# 04-TFCard_SU03T.net
KiCad netlist of a schematic drawn in Altium Designer
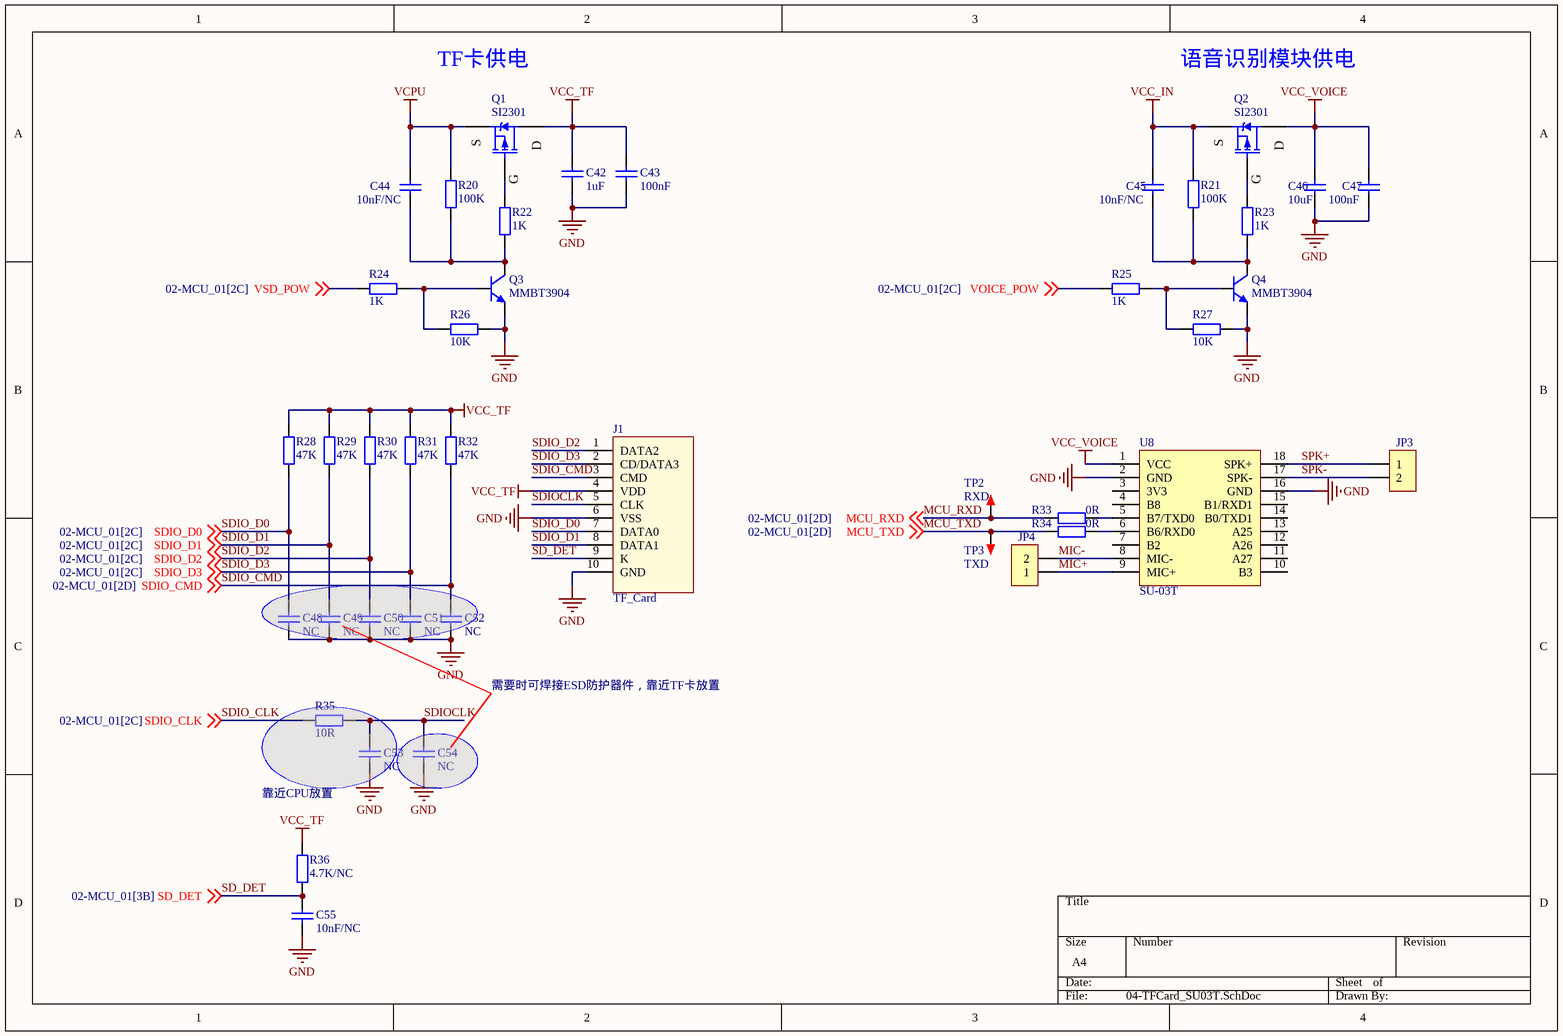
[diagram p0: 04-TFCard_SU03T.SchDoc]

(export (version "E")
  (design (tool "Eeschema 10.0.6"))
  (components
    (comp (ref "C42")
      (value "1uF")
      (footprint "C0603_M")
      (description "贴片电容/MLCC电容")
      (libsource (lib "0.1 - 电阻-电容-电感-保险丝-晶振-晶体-磁珠-电位器-法拉电容-馈通电容") (part "C"))
    )
    (comp (ref "C43")
      (value "100nF")
      (footprint "C0603_M")
      (description "贴片电容/MLCC电容")
      (libsource (lib "0.1 - 电阻-电容-电感-保险丝-晶振-晶体-磁珠-电位器-法拉电容-馈通电容") (part "C"))
    )
    (comp (ref "C44")
      (value "10nF/NC")
      (footprint "C0603_M")
      (description "贴片电容/MLCC电容")
      (libsource (lib "0.1 - 电阻-电容-电感-保险丝-晶振-晶体-磁珠-电位器-法拉电容-馈通电容") (part "C"))
    )
    (comp (ref "C45")
      (value "10nF/NC")
      (footprint "C0603_M")
      (description "贴片电容/MLCC电容")
      (libsource (lib "0.1 - 电阻-电容-电感-保险丝-晶振-晶体-磁珠-电位器-法拉电容-馈通电容") (part "C"))
    )
    (comp (ref "C46")
      (value "10uF")
      (footprint "C0603_M")
      (description "贴片电容/MLCC电容")
      (libsource (lib "0.1 - 电阻-电容-电感-保险丝-晶振-晶体-磁珠-电位器-法拉电容-馈通电容") (part "C"))
    )
    (comp (ref "C47")
      (value "100nF")
      (footprint "C0603_M")
      (description "贴片电容/MLCC电容")
      (libsource (lib "0.1 - 电阻-电容-电感-保险丝-晶振-晶体-磁珠-电位器-法拉电容-馈通电容") (part "C"))
    )
    (comp (ref "C48")
      (value "NC")
      (footprint "C0402_L")
      (description "贴片电容/MLCC电容")
      (libsource (lib "0.1 - 电阻-电容-电感-保险丝-晶振-晶体-磁珠-电位器-法拉电容-馈通电容") (part "C"))
    )
    (comp (ref "C49")
      (value "NC")
      (footprint "C0402_L")
      (description "贴片电容/MLCC电容")
      (libsource (lib "0.1 - 电阻-电容-电感-保险丝-晶振-晶体-磁珠-电位器-法拉电容-馈通电容") (part "C"))
    )
    (comp (ref "C50")
      (value "NC")
      (footprint "C0402_L")
      (description "贴片电容/MLCC电容")
      (libsource (lib "0.1 - 电阻-电容-电感-保险丝-晶振-晶体-磁珠-电位器-法拉电容-馈通电容") (part "C"))
    )
    (comp (ref "C51")
      (value "NC")
      (footprint "C0402_L")
      (description "贴片电容/MLCC电容")
      (libsource (lib "0.1 - 电阻-电容-电感-保险丝-晶振-晶体-磁珠-电位器-法拉电容-馈通电容") (part "C"))
    )
    (comp (ref "C52")
      (value "NC")
      (footprint "C0402_L")
      (description "贴片电容/MLCC电容")
      (libsource (lib "0.1 - 电阻-电容-电感-保险丝-晶振-晶体-磁珠-电位器-法拉电容-馈通电容") (part "C"))
    )
    (comp (ref "C53")
      (value "NC")
      (footprint "C0603_M")
      (description "贴片电容/MLCC电容")
      (libsource (lib "0.1 - 电阻-电容-电感-保险丝-晶振-晶体-磁珠-电位器-法拉电容-馈通电容") (part "C"))
    )
    (comp (ref "C54")
      (value "NC")
      (footprint "C0402_L")
      (description "贴片电容/MLCC电容")
      (libsource (lib "0.1 - 电阻-电容-电感-保险丝-晶振-晶体-磁珠-电位器-法拉电容-馈通电容") (part "C"))
    )
    (comp (ref "C55")
      (value "10nF/NC")
      (footprint "C0603_M")
      (description "贴片电容/MLCC电容")
      (libsource (lib "0.1 - 电阻-电容-电感-保险丝-晶振-晶体-磁珠-电位器-法拉电容-馈通电容") (part "C"))
    )
    (comp (ref "J1")
      (value "TF_Card")
      (footprint "Micro SD")
      (description "TF卡座")
      (libsource (lib "0.6 - 电源_音频_USB Type-C_HDMI_XT60_5557_D-SUB_RJ45_SD-TF_SIM插座") (part "TF_Card"))
    )
    (comp (ref "JP3")
      (value "HDR-1X2")
      (footprint "MX1.25-WT-2P")
      (description "2P连接器")
      (libsource (lib "5.1 - 1.25mm连接器(FPC1.25_GH1.25_MX1.25)") (part "Header 2"))
    )
    (comp (ref "JP4")
      (value "HDR-1X2")
      (footprint "MX1.25-WT-2P")
      (description "2P连接器")
      (libsource (lib "") (part "Header 2_1"))
    )
    (comp (ref "Q1")
      (value "SI2301")
      (footprint "SOT23-3N")
      (description "P沟道 20V/2.8A")
      (libsource (lib "0.4 - 三极管-场效应管-可控硅") (part "SI2301"))
    )
    (comp (ref "Q2")
      (value "SI2301")
      (footprint "SOT23-3N")
      (description "P沟道 20V/2.8A")
      (libsource (lib "0.4 - 三极管-场效应管-可控硅") (part "SI2301"))
    )
    (comp (ref "Q3")
      (value "MMBT3904")
      (footprint "SOT23-3N")
      (description "高频放大-NPN型")
      (libsource (lib "0.4 - 三极管-场效应管-可控硅") (part "MMBT3904"))
    )
    (comp (ref "Q4")
      (value "MMBT3904")
      (footprint "SOT23-3N")
      (description "高频放大-NPN型")
      (libsource (lib "0.4 - 三极管-场效应管-可控硅") (part "MMBT3904"))
    )
    (comp (ref "R20")
      (value "100K")
      (footprint "R0603_M")
      (description "贴片电阻")
      (libsource (lib "0.1 - 电阻-电容-电感-保险丝-晶振-晶体-磁珠-电位器-法拉电容-馈通电容") (part "R"))
    )
    (comp (ref "R21")
      (value "100K")
      (footprint "R0603_M")
      (description "贴片电阻")
      (libsource (lib "0.1 - 电阻-电容-电感-保险丝-晶振-晶体-磁珠-电位器-法拉电容-馈通电容") (part "R"))
    )
    (comp (ref "R22")
      (value "1K")
      (footprint "R0603_M")
      (description "贴片电阻")
      (libsource (lib "0.1 - 电阻-电容-电感-保险丝-晶振-晶体-磁珠-电位器-法拉电容-馈通电容") (part "R"))
    )
    (comp (ref "R23")
      (value "1K")
      (footprint "R0603_M")
      (description "贴片电阻")
      (libsource (lib "0.1 - 电阻-电容-电感-保险丝-晶振-晶体-磁珠-电位器-法拉电容-馈通电容") (part "R"))
    )
    (comp (ref "R24")
      (value "1K")
      (footprint "R0603_M")
      (description "贴片电阻")
      (libsource (lib "0.1 - 电阻-电容-电感-保险丝-晶振-晶体-磁珠-电位器-法拉电容-馈通电容") (part "R"))
    )
    (comp (ref "R25")
      (value "1K")
      (footprint "R0603_M")
      (description "贴片电阻")
      (libsource (lib "0.1 - 电阻-电容-电感-保险丝-晶振-晶体-磁珠-电位器-法拉电容-馈通电容") (part "R"))
    )
    (comp (ref "R26")
      (value "10K")
      (footprint "R0603_M")
      (description "贴片电阻")
      (libsource (lib "0.1 - 电阻-电容-电感-保险丝-晶振-晶体-磁珠-电位器-法拉电容-馈通电容") (part "R"))
    )
    (comp (ref "R27")
      (value "10K")
      (footprint "R0603_M")
      (description "贴片电阻")
      (libsource (lib "0.1 - 电阻-电容-电感-保险丝-晶振-晶体-磁珠-电位器-法拉电容-馈通电容") (part "R"))
    )
    (comp (ref "R28")
      (value "47K")
      (footprint "R0603_M")
      (description "贴片电阻")
      (libsource (lib "0.1 - 电阻-电容-电感-保险丝-晶振-晶体-磁珠-电位器-法拉电容-馈通电容") (part "R"))
    )
    (comp (ref "R29")
      (value "47K")
      (footprint "R0603_M")
      (description "贴片电阻")
      (libsource (lib "0.1 - 电阻-电容-电感-保险丝-晶振-晶体-磁珠-电位器-法拉电容-馈通电容") (part "R"))
    )
    (comp (ref "R30")
      (value "47K")
      (footprint "R0603_M")
      (description "贴片电阻")
      (libsource (lib "0.1 - 电阻-电容-电感-保险丝-晶振-晶体-磁珠-电位器-法拉电容-馈通电容") (part "R"))
    )
    (comp (ref "R31")
      (value "47K")
      (footprint "R0603_M")
      (description "贴片电阻")
      (libsource (lib "0.1 - 电阻-电容-电感-保险丝-晶振-晶体-磁珠-电位器-法拉电容-馈通电容") (part "R"))
    )
    (comp (ref "R32")
      (value "47K")
      (footprint "R0603_M")
      (description "贴片电阻")
      (libsource (lib "0.1 - 电阻-电容-电感-保险丝-晶振-晶体-磁珠-电位器-法拉电容-馈通电容") (part "R"))
    )
    (comp (ref "R33")
      (value "0R")
      (footprint "R0603_M")
      (description "贴片电阻")
      (libsource (lib "0.1 - 电阻-电容-电感-保险丝-晶振-晶体-磁珠-电位器-法拉电容-馈通电容") (part "R"))
    )
    (comp (ref "R34")
      (value "0R")
      (footprint "R0603_M")
      (description "贴片电阻")
      (libsource (lib "0.1 - 电阻-电容-电感-保险丝-晶振-晶体-磁珠-电位器-法拉电容-馈通电容") (part "R"))
    )
    (comp (ref "R35")
      (value "10R")
      (footprint "R0603_M")
      (description "贴片电阻")
      (libsource (lib "0.1 - 电阻-电容-电感-保险丝-晶振-晶体-磁珠-电位器-法拉电容-馈通电容") (part "R"))
    )
    (comp (ref "R36")
      (value "4.7K/NC")
      (footprint "R0603_M")
      (description "贴片电阻")
      (libsource (lib "0.1 - 电阻-电容-电感-保险丝-晶振-晶体-磁珠-电位器-法拉电容-馈通电容") (part "R"))
    )
    (comp (ref "TP2")
      (value "RXD")
      (footprint "TEST 1.6")
      (description "测试点")
      (libsource (lib "0.5 - 按键_开关_蜂鸣器_电池_测试点_Mark点_铜柱") (part "TEST"))
    )
    (comp (ref "TP3")
      (value "TXD")
      (footprint "TEST 1.6")
      (description "测试点")
      (libsource (lib "0.5 - 按键_开关_蜂鸣器_电池_测试点_Mark点_铜柱") (part "TEST"))
    )
    (comp (ref "U8")
      (value "SU-03T")
      (footprint "SU-03T")
      (description "离线语音识别模块V1.8")
      (libsource (lib "0.9 - 传感器-存储器-模块") (part "SU-03T"))
    )
  )
  (nets
    (net (code "1") (name "/MIC+") (class "Default")
      (node (ref "JP4") (pin "1") (pinfunction "1_1") (pintype "passive"))
      (node (ref "U8") (pin "9") (pinfunction "MIC+_9") (pintype "passive"))
    )
    (net (code "2") (name "/MIC-") (class "Default")
      (node (ref "JP4") (pin "2") (pinfunction "2_2") (pintype "passive"))
      (node (ref "U8") (pin "8") (pinfunction "MIC-_8") (pintype "passive"))
    )
    (net (code "3") (name "/SDIOCLK") (class "Default")
      (node (ref "C53") (pin "2") (pinfunction "2_2") (pintype "passive"))
      (node (ref "C54") (pin "2") (pinfunction "2_2") (pintype "passive"))
      (node (ref "J1") (pin "5") (pinfunction "CLK_5") (pintype "passive"))
      (node (ref "R35") (pin "1") (pinfunction "1_1") (pintype "passive"))
    )
    (net (code "4") (name "/SPK+") (class "Default")
      (node (ref "JP3") (pin "1") (pinfunction "1_1") (pintype "passive"))
      (node (ref "U8") (pin "18") (pinfunction "SPK+_18") (pintype "passive"))
    )
    (net (code "5") (name "/SPK-") (class "Default")
      (node (ref "JP3") (pin "2") (pinfunction "2_2") (pintype "passive"))
      (node (ref "U8") (pin "17") (pinfunction "SPK-_17") (pintype "passive"))
    )
    (net (code "6") (name "GND") (class "Default")
      (node (ref "C42") (pin "1") (pinfunction "1_1") (pintype "passive"))
      (node (ref "C43") (pin "1") (pinfunction "1_1") (pintype "passive"))
      (node (ref "C46") (pin "1") (pinfunction "1_1") (pintype "passive"))
      (node (ref "C47") (pin "1") (pinfunction "1_1") (pintype "passive"))
      (node (ref "C48") (pin "1") (pinfunction "1_1") (pintype "passive"))
      (node (ref "C49") (pin "1") (pinfunction "1_1") (pintype "passive"))
      (node (ref "C50") (pin "1") (pinfunction "1_1") (pintype "passive"))
      (node (ref "C51") (pin "1") (pinfunction "1_1") (pintype "passive"))
      (node (ref "C52") (pin "1") (pinfunction "1_1") (pintype "passive"))
      (node (ref "C53") (pin "1") (pinfunction "1_1") (pintype "passive"))
      (node (ref "C54") (pin "1") (pinfunction "1_1") (pintype "passive"))
      (node (ref "C55") (pin "1") (pinfunction "1_1") (pintype "passive"))
      (node (ref "J1") (pin "10") (pinfunction "GND_10") (pintype "passive"))
      (node (ref "J1") (pin "6") (pinfunction "VSS_6") (pintype "passive"))
      (node (ref "Q3") (pin "2") (pinfunction "E_2") (pintype "passive"))
      (node (ref "Q4") (pin "2") (pinfunction "E_2") (pintype "passive"))
      (node (ref "R26") (pin "1") (pinfunction "1_1") (pintype "passive"))
      (node (ref "R27") (pin "1") (pinfunction "1_1") (pintype "passive"))
      (node (ref "U8") (pin "16") (pinfunction "GND_16") (pintype "passive"))
      (node (ref "U8") (pin "2") (pinfunction "GND_2") (pintype "passive"))
    )
    (net (code "7") (name "MCU_RXD") (class "Default")
      (node (ref "R33") (pin "2") (pinfunction "2_2") (pintype "passive"))
      (node (ref "TP2") (pin "1") (pinfunction "1_1") (pintype "passive"))
    )
    (net (code "8") (name "MCU_TXD") (class "Default")
      (node (ref "R34") (pin "2") (pinfunction "2_2") (pintype "passive"))
      (node (ref "TP3") (pin "1") (pinfunction "1_1") (pintype "passive"))
    )
    (net (code "9") (name "Net-(Q1-G)") (class "Default")
      (node (ref "Q1") (pin "1") (pinfunction "G_1") (pintype "passive"))
      (node (ref "R22") (pin "1") (pinfunction "1_1") (pintype "passive"))
    )
    (net (code "10") (name "Net-(Q2-G)") (class "Default")
      (node (ref "Q2") (pin "1") (pinfunction "G_1") (pintype "passive"))
      (node (ref "R23") (pin "1") (pinfunction "1_1") (pintype "passive"))
    )
    (net (code "11") (name "Net-(Q3-B)") (class "Default")
      (node (ref "Q3") (pin "1") (pinfunction "B_1") (pintype "passive"))
      (node (ref "R24") (pin "1") (pinfunction "1_1") (pintype "passive"))
      (node (ref "R26") (pin "2") (pinfunction "2_2") (pintype "passive"))
    )
    (net (code "12") (name "Net-(Q3-C)") (class "Default")
      (node (ref "C44") (pin "1") (pinfunction "1_1") (pintype "passive"))
      (node (ref "Q3") (pin "3") (pinfunction "C_3") (pintype "passive"))
      (node (ref "R20") (pin "2") (pinfunction "2_2") (pintype "passive"))
      (node (ref "R22") (pin "2") (pinfunction "2_2") (pintype "passive"))
    )
    (net (code "13") (name "Net-(Q4-B)") (class "Default")
      (node (ref "Q4") (pin "1") (pinfunction "B_1") (pintype "passive"))
      (node (ref "R25") (pin "1") (pinfunction "1_1") (pintype "passive"))
      (node (ref "R27") (pin "2") (pinfunction "2_2") (pintype "passive"))
    )
    (net (code "14") (name "Net-(Q4-C)") (class "Default")
      (node (ref "C45") (pin "1") (pinfunction "1_1") (pintype "passive"))
      (node (ref "Q4") (pin "3") (pinfunction "C_3") (pintype "passive"))
      (node (ref "R21") (pin "2") (pinfunction "2_2") (pintype "passive"))
      (node (ref "R23") (pin "2") (pinfunction "2_2") (pintype "passive"))
    )
    (net (code "15") (name "Net-(U8-B6{slash}RXD0)") (class "Default")
      (node (ref "R34") (pin "1") (pinfunction "1_1") (pintype "passive"))
      (node (ref "U8") (pin "6") (pinfunction "B6/RXD0_6") (pintype "passive"))
    )
    (net (code "16") (name "Net-(U8-B7{slash}TXD0)") (class "Default")
      (node (ref "R33") (pin "1") (pinfunction "1_1") (pintype "passive"))
      (node (ref "U8") (pin "5") (pinfunction "B7/TXD0_5") (pintype "passive"))
    )
    (net (code "17") (name "SDIO_CLK") (class "Default")
      (node (ref "R35") (pin "2") (pinfunction "2_2") (pintype "passive"))
    )
    (net (code "18") (name "SDIO_CMD") (class "Default")
      (node (ref "C52") (pin "2") (pinfunction "2_2") (pintype "passive"))
      (node (ref "J1") (pin "3") (pinfunction "CMD_3") (pintype "passive"))
      (node (ref "R32") (pin "2") (pinfunction "2_2") (pintype "passive"))
    )
    (net (code "19") (name "SDIO_D0") (class "Default")
      (node (ref "C48") (pin "2") (pinfunction "2_2") (pintype "passive"))
      (node (ref "J1") (pin "7") (pinfunction "DATA0_7") (pintype "passive"))
      (node (ref "R28") (pin "2") (pinfunction "2_2") (pintype "passive"))
    )
    (net (code "20") (name "SDIO_D1") (class "Default")
      (node (ref "C49") (pin "2") (pinfunction "2_2") (pintype "passive"))
      (node (ref "J1") (pin "8") (pinfunction "DATA1_8") (pintype "passive"))
      (node (ref "R29") (pin "2") (pinfunction "2_2") (pintype "passive"))
    )
    (net (code "21") (name "SDIO_D2") (class "Default")
      (node (ref "C50") (pin "2") (pinfunction "2_2") (pintype "passive"))
      (node (ref "J1") (pin "1") (pinfunction "DATA2_1") (pintype "passive"))
      (node (ref "R30") (pin "2") (pinfunction "2_2") (pintype "passive"))
    )
    (net (code "22") (name "SDIO_D3") (class "Default")
      (node (ref "C51") (pin "2") (pinfunction "2_2") (pintype "passive"))
      (node (ref "J1") (pin "2") (pinfunction "CD/DATA3_2") (pintype "passive"))
      (node (ref "R31") (pin "2") (pinfunction "2_2") (pintype "passive"))
    )
    (net (code "23") (name "SD_DET") (class "Default")
      (node (ref "C55") (pin "2") (pinfunction "2_2") (pintype "passive"))
      (node (ref "J1") (pin "9") (pinfunction "K_9") (pintype "passive"))
      (node (ref "R36") (pin "2") (pinfunction "2_2") (pintype "passive"))
    )
    (net (code "24") (name "VCC_IN") (class "Default")
      (node (ref "C45") (pin "2") (pinfunction "2_2") (pintype "passive"))
      (node (ref "Q2") (pin "2") (pinfunction "S_2") (pintype "passive"))
      (node (ref "R21") (pin "1") (pinfunction "1_1") (pintype "passive"))
    )
    (net (code "25") (name "VCC_TF") (class "Default")
      (node (ref "C42") (pin "2") (pinfunction "2_2") (pintype "passive"))
      (node (ref "C43") (pin "2") (pinfunction "2_2") (pintype "passive"))
      (node (ref "J1") (pin "4") (pinfunction "VDD_4") (pintype "passive"))
      (node (ref "Q1") (pin "3") (pinfunction "D_3") (pintype "passive"))
      (node (ref "R28") (pin "1") (pinfunction "1_1") (pintype "passive"))
      (node (ref "R29") (pin "1") (pinfunction "1_1") (pintype "passive"))
      (node (ref "R30") (pin "1") (pinfunction "1_1") (pintype "passive"))
      (node (ref "R31") (pin "1") (pinfunction "1_1") (pintype "passive"))
      (node (ref "R32") (pin "1") (pinfunction "1_1") (pintype "passive"))
      (node (ref "R36") (pin "1") (pinfunction "1_1") (pintype "passive"))
    )
    (net (code "26") (name "VCC_VOICE") (class "Default")
      (node (ref "C46") (pin "2") (pinfunction "2_2") (pintype "passive"))
      (node (ref "C47") (pin "2") (pinfunction "2_2") (pintype "passive"))
      (node (ref "Q2") (pin "3") (pinfunction "D_3") (pintype "passive"))
      (node (ref "U8") (pin "1") (pinfunction "VCC_1") (pintype "passive"))
    )
    (net (code "27") (name "VCPU") (class "Default")
      (node (ref "C44") (pin "2") (pinfunction "2_2") (pintype "passive"))
      (node (ref "Q1") (pin "2") (pinfunction "S_2") (pintype "passive"))
      (node (ref "R20") (pin "1") (pinfunction "1_1") (pintype "passive"))
    )
    (net (code "28") (name "VOICE_POW") (class "Default")
      (node (ref "R25") (pin "2") (pinfunction "2_2") (pintype "passive"))
    )
    (net (code "29") (name "VSD_POW") (class "Default")
      (node (ref "R24") (pin "2") (pinfunction "2_2") (pintype "passive"))
    )
    (net (code "30") (name "unconnected-(U8-3V3-Pad3)") (class "Default")
      (node (ref "U8") (pin "3") (pinfunction "3V3_3") (pintype "passive"))
    )
    (net (code "31") (name "unconnected-(U8-A25-Pad13)") (class "Default")
      (node (ref "U8") (pin "13") (pinfunction "A25_13") (pintype "passive"))
    )
    (net (code "32") (name "unconnected-(U8-A26-Pad12)") (class "Default")
      (node (ref "U8") (pin "12") (pinfunction "A26_12") (pintype "passive"))
    )
    (net (code "33") (name "unconnected-(U8-A27-Pad11)") (class "Default")
      (node (ref "U8") (pin "11") (pinfunction "A27_11") (pintype "passive"))
    )
    (net (code "34") (name "unconnected-(U8-B0{slash}TXD1-Pad14)") (class "Default")
      (node (ref "U8") (pin "14") (pinfunction "B0/TXD1_14") (pintype "passive"))
    )
    (net (code "35") (name "unconnected-(U8-B1{slash}RXD1-Pad15)") (class "Default")
      (node (ref "U8") (pin "15") (pinfunction "B1/RXD1_15") (pintype "passive"))
    )
    (net (code "36") (name "unconnected-(U8-B2-Pad7)") (class "Default")
      (node (ref "U8") (pin "7") (pinfunction "B2_7") (pintype "passive"))
    )
    (net (code "37") (name "unconnected-(U8-B3-Pad10)") (class "Default")
      (node (ref "U8") (pin "10") (pinfunction "B3_10") (pintype "passive"))
    )
    (net (code "38") (name "unconnected-(U8-B8-Pad4)") (class "Default")
      (node (ref "U8") (pin "4") (pinfunction "B8_4") (pintype "passive"))
    )
  )
)
